# photon_at7020_2_rf_test.net
KiCad netlist of a schematic drawn in EAGLE
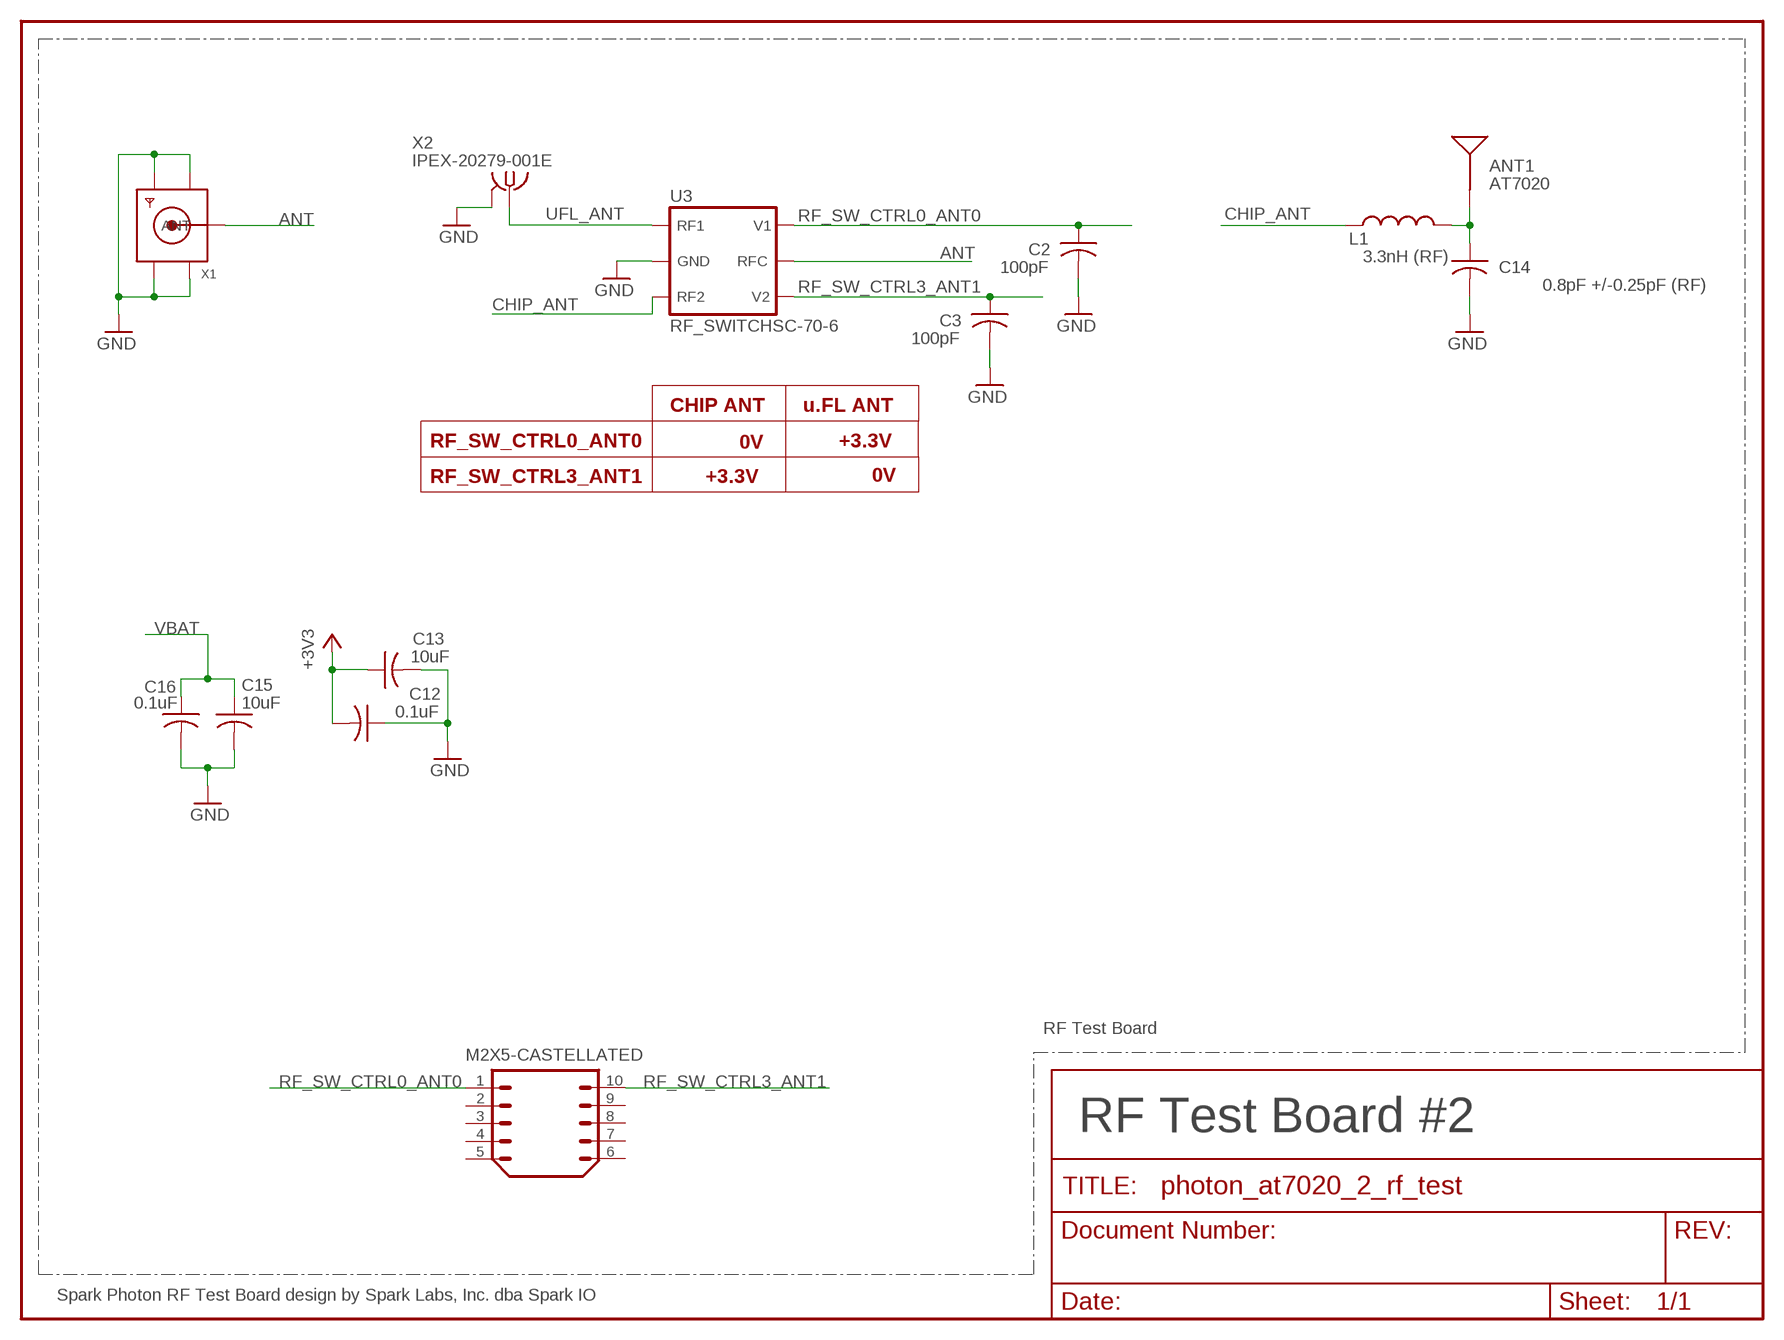
[diagram p0: schematic, sheet 1]

(export (version "E")
  (design (tool "Eeschema 10.0.6"))
  (components
    (comp (ref "ANT1")
      (value "AT7020")
      (footprint "eagle-import:AT7020")
      (libsource (lib "eagle-import") (part "AT7020"))
    )
    (comp (ref "C2")
      (value "100pF")
      (footprint "eagle-import:C0402_B")
      (libsource (lib "eagle-import") (part "C-US"))
    )
    (comp (ref "C3")
      (value "100pF")
      (footprint "eagle-import:C0402_B")
      (libsource (lib "eagle-import") (part "C-US"))
    )
    (comp (ref "C12")
      (value "0.1uF")
      (footprint "eagle-import:C0402_B")
      (libsource (lib "eagle-import") (part "C-US"))
    )
    (comp (ref "C13")
      (value "10uF")
      (footprint "eagle-import:C0402_B")
      (libsource (lib "eagle-import") (part "C-US"))
    )
    (comp (ref "C14")
      (value "0.8pF +/-0.25pF (RF)")
      (footprint "eagle-import:C0402_B")
      (libsource (lib "eagle-import") (part "C-US"))
    )
    (comp (ref "C15")
      (value "10uF")
      (footprint "eagle-import:C0402_B")
      (libsource (lib "eagle-import") (part "C-US"))
    )
    (comp (ref "C16")
      (value "0.1uF")
      (footprint "eagle-import:C0402_B")
      (libsource (lib "eagle-import") (part "C-US"))
    )
    (comp (ref "L1")
      (value "3.3nH (RF)")
      (footprint "eagle-import:L0402_B")
      (libsource (lib "eagle-import") (part "INDUCTOR"))
    )
    (comp (ref "M2X5-CASTELLATED")
      (value "M2X5")
      (footprint "eagle-import:2X5-CASTELLATED")
      (libsource (lib "eagle-import") (part "M2X5"))
    )
    (comp (ref "U3")
      (value "RF_SWITCHSC-70-6")
      (footprint "eagle-import:SC70-6")
      (libsource (lib "eagle-import") (part "RF_SWITCHSC-70-6"))
    )
    (comp (ref "X1")
      (value "SMACONNECTOR_EDGE")
      (footprint "eagle-import:SMA_EDGELAUNCH")
      (libsource (lib "eagle-import") (part "SMACONNECTOR_EDGE"))
    )
    (comp (ref "X2")
      (value "IPEX-20279-001E")
      (footprint "eagle-import:IPEX-20279-001E")
      (libsource (lib "eagle-import") (part "IPEX-20279-001E"))
    )
  )
  (nets
    (net (code "1") (name "+3V3") (class "Default")
      (node (ref "C12") (pin "2") (pinfunction "2_2") (pintype "passive"))
      (node (ref "C13") (pin "1") (pinfunction "1_1") (pintype "passive"))
    )
    (net (code "2") (name "/ANT") (class "Default")
      (node (ref "U3") (pin "5") (pinfunction "RFC_5") (pintype "input"))
      (node (ref "X1") (pin "P") (pinfunction "ANT_P") (pintype "bidirectional"))
    )
    (net (code "3") (name "/CHIP_ANT") (class "Default")
      (node (ref "L1") (pin "1") (pinfunction "1_1") (pintype "passive"))
      (node (ref "U3") (pin "3") (pinfunction "RF2_3") (pintype "output"))
    )
    (net (code "4") (name "/RF_SW_CTRL0_ANT0") (class "Default")
      (node (ref "C2") (pin "1") (pinfunction "1_1") (pintype "passive"))
      (node (ref "M2X5-CASTELLATED") (pin "1") (pinfunction "1_1") (pintype "passive"))
      (node (ref "U3") (pin "6") (pinfunction "V1_6") (pintype "input"))
    )
    (net (code "5") (name "/RF_SW_CTRL3_ANT1") (class "Default")
      (node (ref "C3") (pin "1") (pinfunction "1_1") (pintype "passive"))
      (node (ref "M2X5-CASTELLATED") (pin "10") (pinfunction "10_10") (pintype "passive"))
      (node (ref "U3") (pin "4") (pinfunction "V2_4") (pintype "input"))
    )
    (net (code "6") (name "/UFL_ANT") (class "Default")
      (node (ref "U3") (pin "1") (pinfunction "RF1_1") (pintype "output"))
      (node (ref "X2") (pin "1") (pinfunction "1_1") (pintype "passive"))
    )
    (net (code "7") (name "/VBAT") (class "Default")
      (node (ref "C15") (pin "1") (pinfunction "1_1") (pintype "passive"))
      (node (ref "C16") (pin "1") (pinfunction "1_1") (pintype "passive"))
    )
    (net (code "8") (name "GND") (class "Default")
      (node (ref "C12") (pin "1") (pinfunction "1_1") (pintype "passive"))
      (node (ref "C13") (pin "2") (pinfunction "2_2") (pintype "passive"))
      (node (ref "C14") (pin "2") (pinfunction "2_2") (pintype "passive"))
      (node (ref "C15") (pin "2") (pinfunction "2_2") (pintype "passive"))
      (node (ref "C16") (pin "2") (pinfunction "2_2") (pintype "passive"))
      (node (ref "C2") (pin "2") (pinfunction "2_2") (pintype "passive"))
      (node (ref "C3") (pin "2") (pinfunction "2_2") (pintype "passive"))
      (node (ref "U3") (pin "2") (pinfunction "GND_2") (pintype "power_in"))
      (node (ref "X1") (pin "GND@1") (pinfunction "GND4_GND@1") (pintype "power_in"))
      (node (ref "X1") (pin "GND@2") (pinfunction "GND3_GND@2") (pintype "power_in"))
      (node (ref "X1") (pin "GND@3") (pinfunction "GND2_GND@3") (pintype "power_in"))
      (node (ref "X1") (pin "GND@4") (pinfunction "GND1_GND@4") (pintype "power_in"))
      (node (ref "X2") (pin "2@1") (pinfunction "GND_2@1") (pintype "passive"))
      (node (ref "X2") (pin "2@2") (pinfunction "GND_2@2") (pintype "passive"))
    )
    (net (code "9") (name "Net-(ANT1-SIGNAL)") (class "Default")
      (node (ref "ANT1") (pin "1") (pinfunction "SIGNAL_1") (pintype "bidirectional"))
      (node (ref "C14") (pin "1") (pinfunction "1_1") (pintype "passive"))
      (node (ref "L1") (pin "2") (pinfunction "2_2") (pintype "passive"))
    )
    (net (code "10") (name "unconnected-(M2X5-CASTELLATED-Pad2)") (class "Default")
      (node (ref "M2X5-CASTELLATED") (pin "2") (pinfunction "2_2") (pintype "passive"))
    )
    (net (code "11") (name "unconnected-(M2X5-CASTELLATED-Pad3)") (class "Default")
      (node (ref "M2X5-CASTELLATED") (pin "3") (pinfunction "3_3") (pintype "passive"))
    )
    (net (code "12") (name "unconnected-(M2X5-CASTELLATED-Pad4)") (class "Default")
      (node (ref "M2X5-CASTELLATED") (pin "4") (pinfunction "4_4") (pintype "passive"))
    )
    (net (code "13") (name "unconnected-(M2X5-CASTELLATED-Pad5)") (class "Default")
      (node (ref "M2X5-CASTELLATED") (pin "5") (pinfunction "5_5") (pintype "passive"))
    )
    (net (code "14") (name "unconnected-(M2X5-CASTELLATED-Pad6)") (class "Default")
      (node (ref "M2X5-CASTELLATED") (pin "6") (pinfunction "6_6") (pintype "passive"))
    )
    (net (code "15") (name "unconnected-(M2X5-CASTELLATED-Pad7)") (class "Default")
      (node (ref "M2X5-CASTELLATED") (pin "7") (pinfunction "7_7") (pintype "passive"))
    )
    (net (code "16") (name "unconnected-(M2X5-CASTELLATED-Pad8)") (class "Default")
      (node (ref "M2X5-CASTELLATED") (pin "8") (pinfunction "8_8") (pintype "passive"))
    )
    (net (code "17") (name "unconnected-(M2X5-CASTELLATED-Pad9)") (class "Default")
      (node (ref "M2X5-CASTELLATED") (pin "9") (pinfunction "9_9") (pintype "passive"))
    )
  )
)
